# ADXL_343.net
KiCad netlist of a schematic drawn in Altium Designer
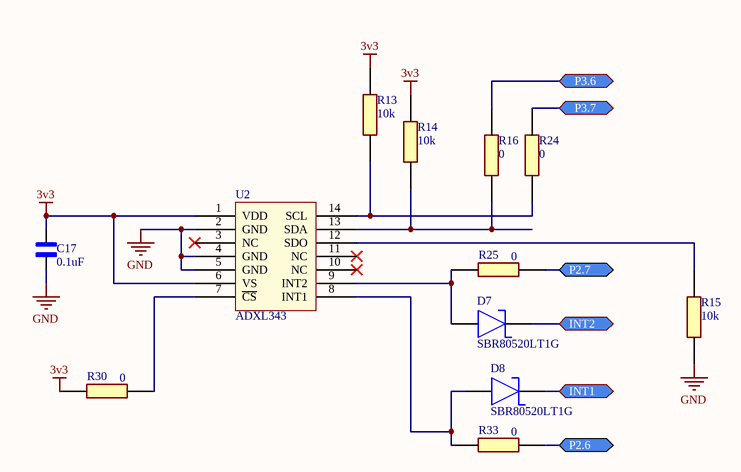
[diagram p0: ADXL 343.SchDoc]

(export (version "E")
  (design (tool "Eeschema 10.0.6"))
  (components
    (comp (ref "C17")
      (value "0.1uF")
      (footprint "CAPC1005X55N")
      (description "Capacitor X6S 0402 (1005 Metric)")
      (fields (field (name "MANUFACTURER") "Murata Electronics") (field (name "TOLERANCE") "10%"))
      (libsource (lib "UngBung") (part "Multilayer Ceramic Cap. 0402 (1005 Metric)"))
    )
    (comp (ref "D7")
      (value "SBR80520LT1G")
      (footprint "Diode SOD-123-2")
      (description "Schottky Diodes & Rectifiers REC SPCL SKTKY")
      (fields (field (name "MANUFACTURER") "ON Semiconductor"))
      (libsource (lib "UngBung") (part "SBR80520LT1G"))
    )
    (comp (ref "D8")
      (value "SBR80520LT1G")
      (footprint "Diode SOD-123-2")
      (description "Schottky Diodes & Rectifiers REC SPCL SKTKY")
      (fields (field (name "MANUFACTURER") "ON Semiconductor"))
      (libsource (lib "UngBung") (part "SBR80520LT1G"))
    )
    (comp (ref "R13")
      (value "10k")
      (footprint "Thin-Film Resistor 0402 (1005 Metric)")
      (description "Resistor, 0402 Package size")
      (fields (field (name "MANUFACTURER") "Vishay / Dale") (field (name "TOLERANCE") "1%"))
      (libsource (lib "UngBung") (part "Resistor 0402 (1005 Metric)"))
    )
    (comp (ref "R14")
      (value "10k")
      (footprint "Thin-Film Resistor 0402 (1005 Metric)")
      (description "Resistor, 0402 Package size")
      (fields (field (name "MANUFACTURER") "Vishay / Dale") (field (name "TOLERANCE") "1%"))
      (libsource (lib "UngBung") (part "Resistor 0402 (1005 Metric)"))
    )
    (comp (ref "R15")
      (value "10k")
      (footprint "Thin-Film Resistor 0402 (1005 Metric)")
      (description "Resistor, 0402 Package size")
      (fields (field (name "MANUFACTURER") "Vishay / Dale") (field (name "TOLERANCE") "1%"))
      (libsource (lib "UngBung") (part "Resistor 0402 (1005 Metric)"))
    )
    (comp (ref "R16")
      (value "0")
      (footprint "Resistor 0603")
      (fields (field (name "TOLERANCE") "*tolerance*") (field (name "Comment") "Resistor 0603"))
      (libsource (lib "UngBung") (part "Resistor 0603"))
    )
    (comp (ref "R24")
      (value "0")
      (footprint "Resistor 0603")
      (fields (field (name "TOLERANCE") "*tolerance*") (field (name "Comment") "Resistor 0603"))
      (libsource (lib "UngBung") (part "Resistor 0603"))
    )
    (comp (ref "R25")
      (value "0")
      (footprint "Resistor 0603")
      (fields (field (name "TOLERANCE") "*tolerance*") (field (name "Comment") "Resistor 0603"))
      (libsource (lib "") (part "Resistor 0603_1"))
    )
    (comp (ref "R30")
      (value "0")
      (footprint "Resistor 0603")
      (fields (field (name "TOLERANCE") "*tolerance*") (field (name "Comment") "Resistor 0603"))
      (libsource (lib "") (part "Resistor 0603_1"))
    )
    (comp (ref "R33")
      (value "0")
      (footprint "Resistor 0603")
      (fields (field (name "TOLERANCE") "*tolerance*") (field (name "Comment") "Resistor 0603"))
      (libsource (lib "") (part "Resistor 0603_1"))
    )
    (comp (ref "U2")
      (value "ADXL343")
      (footprint "ADXL343")
      (description "Accelerometer X, Y, Z Axis ±2g, 4g, 8g, 16g 0.05Hz ~ 1.6kHz 14-LGA (3x5)")
      (fields (field (name "MANUFACTURER") "Analog Devices Inc."))
      (libsource (lib "UngBung") (part "ADXL343"))
    )
  )
  (nets
    (net (code "1") (name "/INT1") (class "Default")
      (node (ref "D8") (pin "1") (pinfunction "K_1") (pintype "passive"))
    )
    (net (code "2") (name "/INT2") (class "Default")
      (node (ref "D7") (pin "1") (pinfunction "K_1") (pintype "passive"))
    )
    (net (code "3") (name "/P2.6") (class "Default")
      (node (ref "R33") (pin "1") (pinfunction "1_1") (pintype "passive"))
    )
    (net (code "4") (name "/P2.7") (class "Default")
      (node (ref "R25") (pin "1") (pinfunction "1_1") (pintype "passive"))
    )
    (net (code "5") (name "/P3.6") (class "Default")
      (node (ref "R16") (pin "2") (pinfunction "2_2") (pintype "passive"))
    )
    (net (code "6") (name "/P3.7") (class "Default")
      (node (ref "R24") (pin "2") (pinfunction "2_2") (pintype "passive"))
    )
    (net (code "7") (name "3v3") (class "Default")
      (node (ref "C17") (pin "2") (pinfunction "2_2") (pintype "passive"))
      (node (ref "R13") (pin "2") (pinfunction "2_2") (pintype "passive"))
      (node (ref "R14") (pin "2") (pinfunction "2_2") (pintype "passive"))
      (node (ref "R30") (pin "2") (pinfunction "2_2") (pintype "passive"))
      (node (ref "U2") (pin "1") (pinfunction "VDD_1") (pintype "passive"))
      (node (ref "U2") (pin "6") (pinfunction "VS_6") (pintype "passive"))
    )
    (net (code "8") (name "GND") (class "Default")
      (node (ref "C17") (pin "1") (pinfunction "1_1") (pintype "passive"))
      (node (ref "R15") (pin "1") (pinfunction "1_1") (pintype "passive"))
      (node (ref "U2") (pin "2") (pinfunction "GND_2") (pintype "passive"))
      (node (ref "U2") (pin "4") (pinfunction "GND_4") (pintype "passive"))
      (node (ref "U2") (pin "5") (pinfunction "GND_5") (pintype "passive"))
    )
    (net (code "9") (name "Net-(D7-A)") (class "Default")
      (node (ref "D7") (pin "2") (pinfunction "A_2") (pintype "passive"))
      (node (ref "R25") (pin "2") (pinfunction "2_2") (pintype "passive"))
      (node (ref "U2") (pin "9") (pinfunction "INT2_9") (pintype "passive"))
    )
    (net (code "10") (name "Net-(D8-A)") (class "Default")
      (node (ref "D8") (pin "2") (pinfunction "A_2") (pintype "passive"))
      (node (ref "R33") (pin "2") (pinfunction "2_2") (pintype "passive"))
      (node (ref "U2") (pin "8") (pinfunction "INT1_8") (pintype "passive"))
    )
    (net (code "11") (name "Net-(U2-SCL)") (class "Default")
      (node (ref "R13") (pin "1") (pinfunction "1_1") (pintype "passive"))
      (node (ref "R24") (pin "1") (pinfunction "1_1") (pintype "passive"))
      (node (ref "U2") (pin "14") (pinfunction "SCL_14") (pintype "passive"))
    )
    (net (code "12") (name "Net-(U2-SDA)") (class "Default")
      (node (ref "R14") (pin "1") (pinfunction "1_1") (pintype "passive"))
      (node (ref "R16") (pin "1") (pinfunction "1_1") (pintype "passive"))
      (node (ref "U2") (pin "13") (pinfunction "SDA_13") (pintype "passive"))
    )
    (net (code "13") (name "Net-(U2-SDO)") (class "Default")
      (node (ref "R15") (pin "2") (pinfunction "2_2") (pintype "passive"))
      (node (ref "U2") (pin "12") (pinfunction "SDO_12") (pintype "passive"))
    )
    (net (code "14") (name "Net-(U2-~{CS})") (class "Default")
      (node (ref "R30") (pin "1") (pinfunction "1_1") (pintype "passive"))
      (node (ref "U2") (pin "7") (pinfunction "~{CS}_7") (pintype "passive"))
    )
    (net (code "15") (name "unconnected-(U2-NC-Pad3)") (class "Default")
      (node (ref "U2") (pin "3") (pinfunction "NC_3") (pintype "passive+no_connect"))
    )
    (net (code "16") (name "unconnected-(U2-NC-Pad10)") (class "Default")
      (node (ref "U2") (pin "10") (pinfunction "NC_10") (pintype "passive+no_connect"))
    )
    (net (code "17") (name "unconnected-(U2-NC-Pad11)") (class "Default")
      (node (ref "U2") (pin "11") (pinfunction "NC_11") (pintype "passive+no_connect"))
    )
  )
)
